# ESP_Batt_Board.net
KiCad netlist of a schematic drawn in Altium Designer
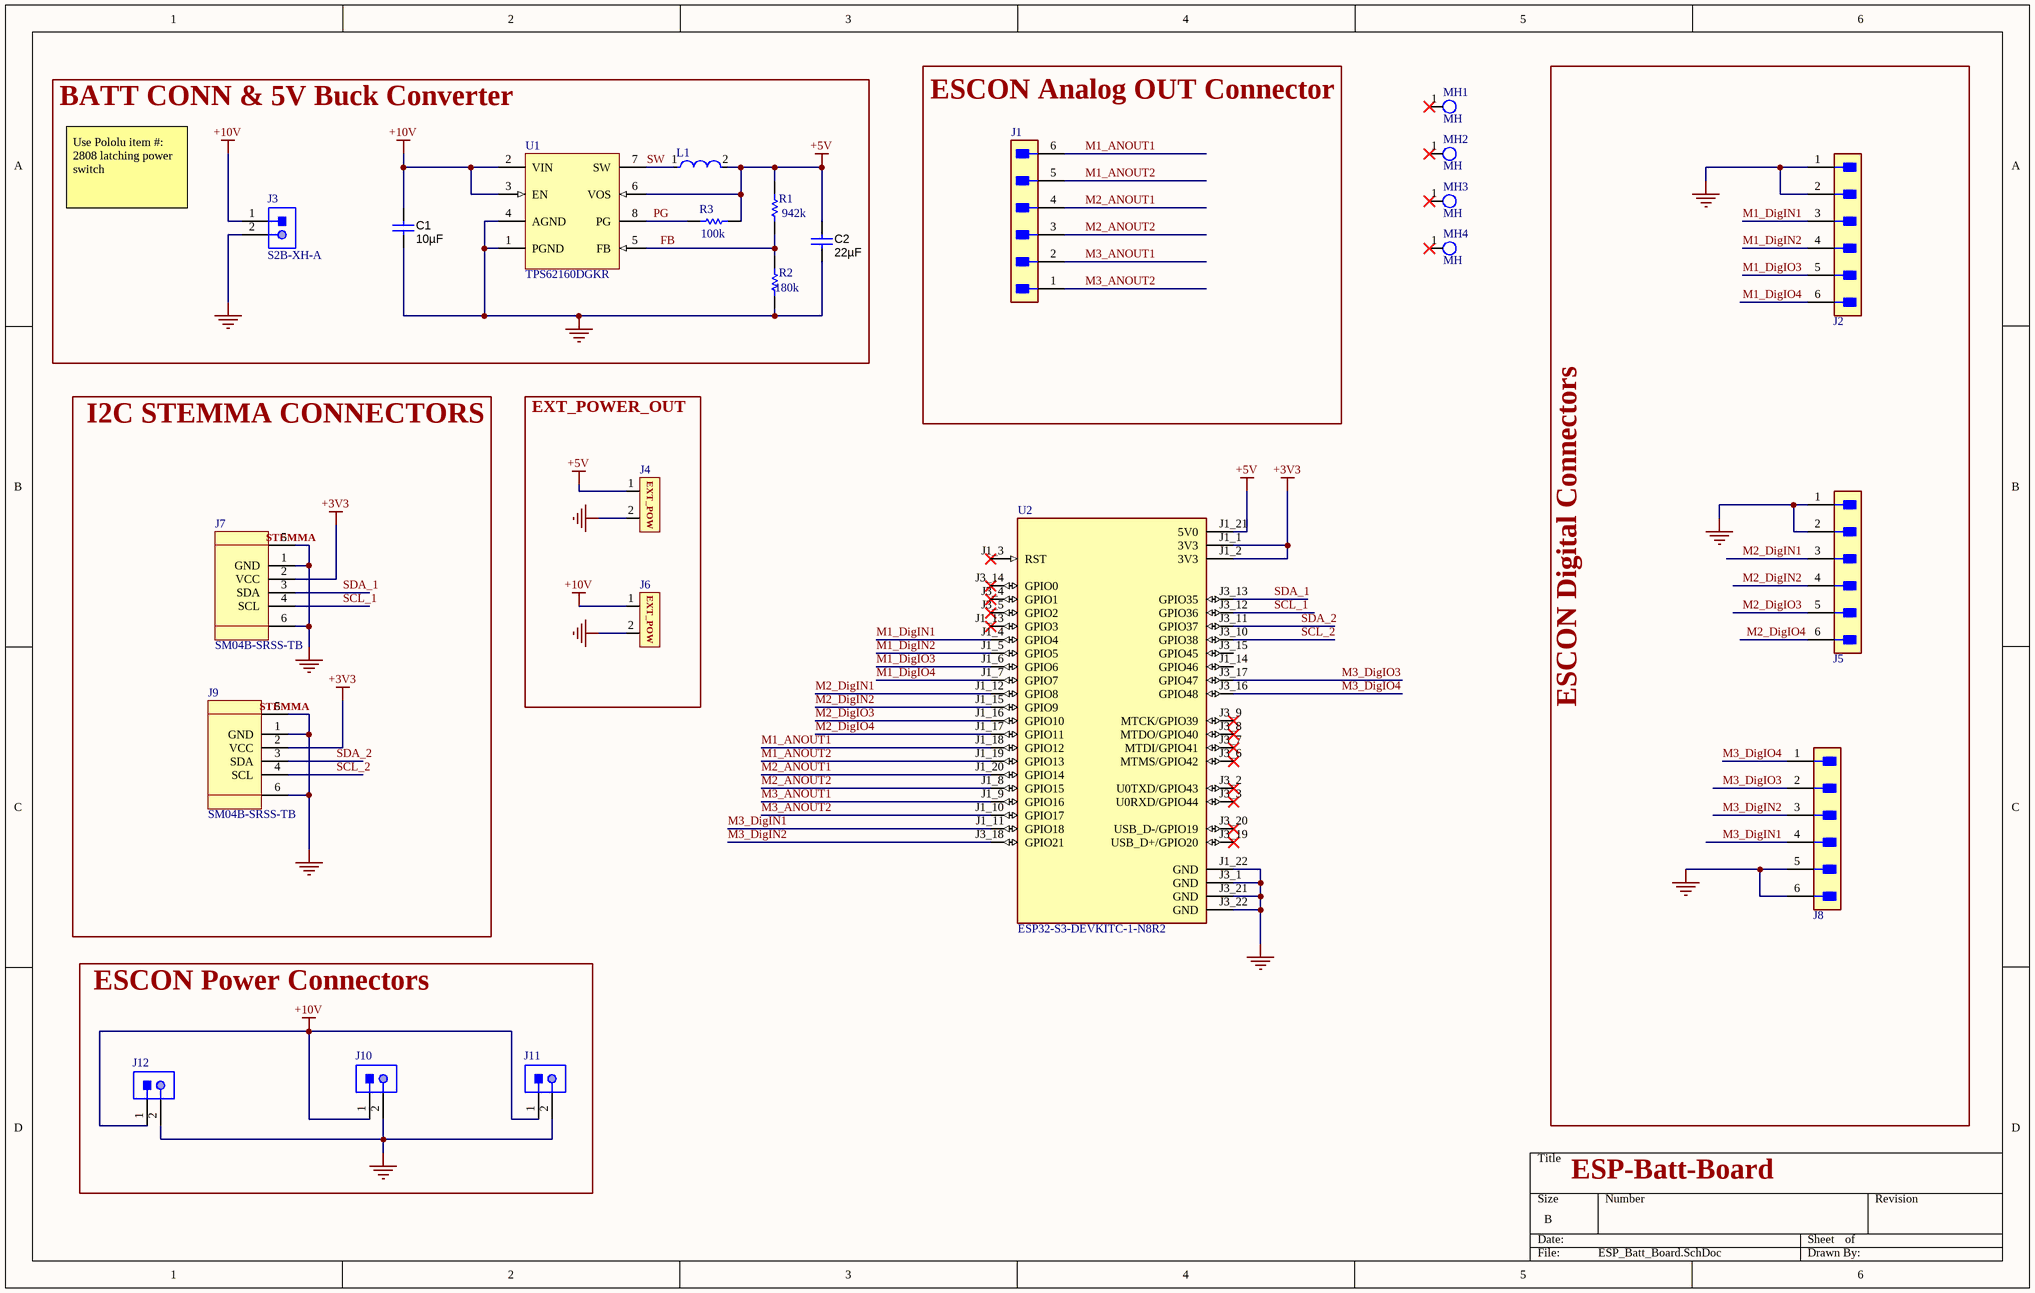
[diagram p0: ESP_Batt_Board.SchDoc]

(export (version "E")
  (design (tool "Eeschema 10.0.6"))
  (components
    (comp (ref "C1")
      (value "C2012X5R1E106K125AB")
      (footprint "CAP_0805")
      (description "CAP, CERM, 10uF, 25V, +/-10%, X5R, 0805")
      (fields
        (field (name "MANUFACTURER") "TDK")
        (field (name "VALUEDISPLAYED") "10µF")
        (field (name "PUBLISHER") "Texas Instruments")
      )
      (libsource (lib "SchematicLib") (part "C2012X5R1E106K125AB"))
    )
    (comp (ref "C2")
      (value "GRM21BR61E226ME44")
      (footprint "CAP_0805")
      (description "CAP, CERM, 22 µF, 25 V, +/- 20%, X5R, 0805")
      (fields (field (name "MANUFACTURER") "MuRata") (field (name "VALUEDISPLAYED") "22µF"))
      (libsource (lib "SchematicLib") (part "GRM21BR61E226ME44"))
    )
    (comp (ref "J1")
      (value "S6B-XH-A (LF)(SN)")
      (footprint "JST-XH-6PIN_RA")
      (description "CONN HEADER THT R/A 6POS 2.5MM")
      (libsource (lib "") (part "S6B-XH-A (LF)(SN)_1"))
    )
    (comp (ref "J2")
      (value "S6B-XH-A (LF)(SN)")
      (footprint "JST-XH-6PIN_RA")
      (description "CONN HEADER THT R/A 6POS 2.5MM")
      (libsource (lib "SchematicLib") (part "S6B-XH-A (LF)(SN)"))
    )
    (comp (ref "J3")
      (value "S2B-XH-A")
      (footprint "JST-S2B-XH-A(LF)(SN)_V")
      (libsource (lib "") (part "S2B-XH-A_1"))
    )
    (comp (ref "J4")
      (value "EXT_POWER_CONN")
      (footprint "PcbLib:POWER")
      (libsource (lib "SchematicLib") (part "EXT_POWER_CONN"))
    )
    (comp (ref "J5")
      (value "S6B-XH-A (LF)(SN)")
      (footprint "JST-XH-6PIN_RA")
      (description "CONN HEADER THT R/A 6POS 2.5MM")
      (libsource (lib "SchematicLib") (part "S6B-XH-A (LF)(SN)"))
    )
    (comp (ref "J6")
      (value "EXT_POWER_CONN")
      (footprint "PcbLib:POWER")
      (libsource (lib "SchematicLib") (part "EXT_POWER_CONN"))
    )
    (comp (ref "J7")
      (value "SM04B-SRSS-TB")
      (footprint "4PIN_STEMMA")
      (libsource (lib "SchematicLib") (part "SM04B-SRSS-TB"))
    )
    (comp (ref "J8")
      (value "S6B-XH-A (LF)(SN)")
      (footprint "JST-XH-6PIN_RA")
      (description "CONN HEADER THT R/A 6POS 2.5MM")
      (libsource (lib "SchematicLib") (part "S6B-XH-A (LF)(SN)"))
    )
    (comp (ref "J9")
      (value "SM04B-SRSS-TB")
      (footprint "4PIN_STEMMA")
      (libsource (lib "SchematicLib") (part "SM04B-SRSS-TB"))
    )
    (comp (ref "J10")
      (value "S2B-XH-A")
      (footprint "JST-S2B-XH-A(LF)(SN)_V")
      (libsource (lib "SchematicLib") (part "S2B-XH-A"))
    )
    (comp (ref "J11")
      (value "S2B-XH-A")
      (footprint "JST-S2B-XH-A(LF)(SN)_V")
      (libsource (lib "SchematicLib") (part "S2B-XH-A"))
    )
    (comp (ref "J12")
      (value "S2B-XH-A")
      (footprint "JST-S2B-XH-A(LF)(SN)_V")
      (libsource (lib "SchematicLib") (part "S2B-XH-A"))
    )
    (comp (ref "L1")
      (value "IHLP1212BZEZ2R2M1Z")
      (footprint "IND_1212")
      (libsource (lib "SchematicLib") (part "IHLP1212BZEZ2R2M1Z"))
    )
    (comp (ref "MH1") (value "MH") (footprint "M2_MTH") (libsource (lib "SchematicLib") (part "M2_MTH")))
    (comp (ref "MH2") (value "MH") (footprint "M2_MTH") (libsource (lib "SchematicLib") (part "M2_MTH")))
    (comp (ref "MH3") (value "MH") (footprint "M2_MTH") (libsource (lib "SchematicLib") (part "M2_MTH")))
    (comp (ref "MH4") (value "MH") (footprint "M2_MTH") (libsource (lib "SchematicLib") (part "M2_MTH")))
    (comp (ref "R1")
      (value "942k")
      (footprint "RES_0603")
      (fields (field (name "R") "942k"))
      (libsource (lib "SchematicLib") (part "RES_0603"))
    )
    (comp (ref "R2")
      (value "180k")
      (footprint "RES_0603")
      (fields (field (name "R") "180k"))
      (libsource (lib "SchematicLib") (part "RES_0603"))
    )
    (comp (ref "R3") (value "100k") (footprint "RES_0603") (libsource (lib "SchematicLib") (part "RES_0603")))
    (comp (ref "U1")
      (value "TPS62160DGKR")
      (footprint "DGK0008A_M")
      (fields (field (name "MANUFACTURER") "Texas Instruments"))
      (libsource (lib "SchematicLib") (part "TPS62160DGKR"))
    )
    (comp (ref "U2")
      (value "ESP32-S3-DEVKITC-1-N8R2")
      (footprint "XCVR_ESP32-S3-DEVKITC-1-N8R2")
      (fields (field (name "MF") "Espressif Systems"))
      (libsource (lib "SchematicLib") (part "ESP32-S3-DEVKITC-1-N8R2"))
    )
  )
  (nets
    (net (code "1") (name "+3V3") (class "Default")
      (node (ref "J7") (pin "2") (pinfunction "VCC_2") (pintype "passive"))
      (node (ref "J9") (pin "2") (pinfunction "VCC_2") (pintype "passive"))
      (node (ref "U2") (pin "J1_1") (pinfunction "3V3_J1_1") (pintype "power_in"))
      (node (ref "U2") (pin "J1_2") (pinfunction "3V3_J1_2") (pintype "power_in"))
    )
    (net (code "2") (name "+5V") (class "Default")
      (node (ref "C2") (pin "1") (pinfunction "1_1") (pintype "passive"))
      (node (ref "J4") (pin "1") (pinfunction "1_1") (pintype "passive"))
      (node (ref "L1") (pin "2") (pinfunction "2_2") (pintype "passive"))
      (node (ref "R1") (pin "2") (pinfunction "2_2") (pintype "passive"))
      (node (ref "R3") (pin "2") (pinfunction "2_2") (pintype "passive"))
      (node (ref "U1") (pin "6") (pinfunction "VOS_6") (pintype "input"))
      (node (ref "U2") (pin "J1_21") (pinfunction "5V0_J1_21") (pintype "power_in"))
    )
    (net (code "3") (name "+10V") (class "Default")
      (node (ref "C1") (pin "1") (pinfunction "1_1") (pintype "passive"))
      (node (ref "J10") (pin "1") (pinfunction "1_1") (pintype "passive"))
      (node (ref "J11") (pin "1") (pinfunction "1_1") (pintype "passive"))
      (node (ref "J12") (pin "1") (pinfunction "1_1") (pintype "passive"))
      (node (ref "J3") (pin "1") (pinfunction "1_1") (pintype "passive"))
      (node (ref "J6") (pin "1") (pinfunction "1_1") (pintype "passive"))
      (node (ref "U1") (pin "2") (pinfunction "VIN_2") (pintype "power_in"))
      (node (ref "U1") (pin "3") (pinfunction "EN_3") (pintype "input"))
    )
    (net (code "4") (name "/FB") (class "Default")
      (node (ref "R1") (pin "1") (pinfunction "1_1") (pintype "passive"))
      (node (ref "R2") (pin "2") (pinfunction "2_2") (pintype "passive"))
      (node (ref "U1") (pin "5") (pinfunction "FB_5") (pintype "input"))
    )
    (net (code "5") (name "/M1_ANOUT1") (class "Default")
      (node (ref "J1") (pin "6") (pinfunction "6_6") (pintype "passive"))
      (node (ref "U2") (pin "J1_18") (pinfunction "GPIO12_J1_18") (pintype "bidirectional"))
    )
    (net (code "6") (name "/M1_ANOUT2") (class "Default")
      (node (ref "J1") (pin "5") (pinfunction "5_5") (pintype "passive"))
      (node (ref "U2") (pin "J1_19") (pinfunction "GPIO13_J1_19") (pintype "bidirectional"))
    )
    (net (code "7") (name "/M1_DigIN1") (class "Default")
      (node (ref "J2") (pin "3") (pinfunction "3_3") (pintype "passive"))
      (node (ref "U2") (pin "J1_4") (pinfunction "GPIO4_J1_4") (pintype "bidirectional"))
    )
    (net (code "8") (name "/M1_DigIN2") (class "Default")
      (node (ref "J2") (pin "4") (pinfunction "4_4") (pintype "passive"))
      (node (ref "U2") (pin "J1_5") (pinfunction "GPIO5_J1_5") (pintype "bidirectional"))
    )
    (net (code "9") (name "/M1_DigIO3") (class "Default")
      (node (ref "J2") (pin "5") (pinfunction "5_5") (pintype "passive"))
      (node (ref "U2") (pin "J1_6") (pinfunction "GPIO6_J1_6") (pintype "bidirectional"))
    )
    (net (code "10") (name "/M1_DigIO4") (class "Default")
      (node (ref "J2") (pin "6") (pinfunction "6_6") (pintype "passive"))
      (node (ref "U2") (pin "J1_7") (pinfunction "GPIO7_J1_7") (pintype "bidirectional"))
    )
    (net (code "11") (name "/M2_ANOUT1") (class "Default")
      (node (ref "J1") (pin "4") (pinfunction "4_4") (pintype "passive"))
      (node (ref "U2") (pin "J1_20") (pinfunction "GPIO14_J1_20") (pintype "bidirectional"))
    )
    (net (code "12") (name "/M2_ANOUT2") (class "Default")
      (node (ref "J1") (pin "3") (pinfunction "3_3") (pintype "passive"))
      (node (ref "U2") (pin "J1_8") (pinfunction "GPIO15_J1_8") (pintype "bidirectional"))
    )
    (net (code "13") (name "/M2_DigIN1") (class "Default")
      (node (ref "J5") (pin "3") (pinfunction "3_3") (pintype "passive"))
      (node (ref "U2") (pin "J1_12") (pinfunction "GPIO8_J1_12") (pintype "bidirectional"))
    )
    (net (code "14") (name "/M2_DigIN2") (class "Default")
      (node (ref "J5") (pin "4") (pinfunction "4_4") (pintype "passive"))
      (node (ref "U2") (pin "J1_15") (pinfunction "GPIO9_J1_15") (pintype "bidirectional"))
    )
    (net (code "15") (name "/M2_DigIO3") (class "Default")
      (node (ref "J5") (pin "5") (pinfunction "5_5") (pintype "passive"))
      (node (ref "U2") (pin "J1_16") (pinfunction "GPIO10_J1_16") (pintype "bidirectional"))
    )
    (net (code "16") (name "/M2_DigIO4") (class "Default")
      (node (ref "J5") (pin "6") (pinfunction "6_6") (pintype "passive"))
      (node (ref "U2") (pin "J1_17") (pinfunction "GPIO11_J1_17") (pintype "bidirectional"))
    )
    (net (code "17") (name "/M3_ANOUT1") (class "Default")
      (node (ref "J1") (pin "2") (pinfunction "2_2") (pintype "passive"))
      (node (ref "U2") (pin "J1_9") (pinfunction "GPIO16_J1_9") (pintype "bidirectional"))
    )
    (net (code "18") (name "/M3_ANOUT2") (class "Default")
      (node (ref "J1") (pin "1") (pinfunction "1_1") (pintype "passive"))
      (node (ref "U2") (pin "J1_10") (pinfunction "GPIO17_J1_10") (pintype "bidirectional"))
    )
    (net (code "19") (name "/M3_DigIN1") (class "Default")
      (node (ref "J8") (pin "4") (pinfunction "4_4") (pintype "passive"))
      (node (ref "U2") (pin "J1_11") (pinfunction "GPIO18_J1_11") (pintype "bidirectional"))
    )
    (net (code "20") (name "/M3_DigIN2") (class "Default")
      (node (ref "J8") (pin "3") (pinfunction "3_3") (pintype "passive"))
      (node (ref "U2") (pin "J3_18") (pinfunction "GPIO21_J3_18") (pintype "bidirectional"))
    )
    (net (code "21") (name "/M3_DigIO3") (class "Default")
      (node (ref "J8") (pin "2") (pinfunction "2_2") (pintype "passive"))
      (node (ref "U2") (pin "J3_17") (pinfunction "GPIO47_J3_17") (pintype "bidirectional"))
    )
    (net (code "22") (name "/M3_DigIO4") (class "Default")
      (node (ref "J8") (pin "1") (pinfunction "1_1") (pintype "passive"))
      (node (ref "U2") (pin "J3_16") (pinfunction "GPIO48_J3_16") (pintype "bidirectional"))
    )
    (net (code "23") (name "/PG") (class "Default")
      (node (ref "R3") (pin "1") (pinfunction "1_1") (pintype "passive"))
      (node (ref "U1") (pin "8") (pinfunction "PG_8") (pintype "tri_state"))
    )
    (net (code "24") (name "/SCL_1") (class "Default")
      (node (ref "J7") (pin "4") (pinfunction "SCL_4") (pintype "passive"))
      (node (ref "U2") (pin "J3_12") (pinfunction "GPIO36_J3_12") (pintype "bidirectional"))
    )
    (net (code "25") (name "/SCL_2") (class "Default")
      (node (ref "J9") (pin "4") (pinfunction "SCL_4") (pintype "passive"))
      (node (ref "U2") (pin "J3_10") (pinfunction "GPIO38_J3_10") (pintype "bidirectional"))
    )
    (net (code "26") (name "/SDA_1") (class "Default")
      (node (ref "J7") (pin "3") (pinfunction "SDA_3") (pintype "passive"))
      (node (ref "U2") (pin "J3_13") (pinfunction "GPIO35_J3_13") (pintype "bidirectional"))
    )
    (net (code "27") (name "/SDA_2") (class "Default")
      (node (ref "J9") (pin "3") (pinfunction "SDA_3") (pintype "passive"))
      (node (ref "U2") (pin "J3_11") (pinfunction "GPIO37_J3_11") (pintype "bidirectional"))
    )
    (net (code "28") (name "/SW") (class "Default")
      (node (ref "L1") (pin "1") (pinfunction "1_1") (pintype "passive"))
      (node (ref "U1") (pin "7") (pinfunction "SW_7") (pintype "power_in"))
    )
    (net (code "29") (name "GND") (class "Default")
      (node (ref "C1") (pin "2") (pinfunction "2_2") (pintype "passive"))
      (node (ref "C2") (pin "2") (pinfunction "2_2") (pintype "passive"))
      (node (ref "J10") (pin "2") (pinfunction "2_2") (pintype "passive"))
      (node (ref "J11") (pin "2") (pinfunction "2_2") (pintype "passive"))
      (node (ref "J12") (pin "2") (pinfunction "2_2") (pintype "passive"))
      (node (ref "J2") (pin "1") (pinfunction "1_1") (pintype "passive"))
      (node (ref "J2") (pin "2") (pinfunction "2_2") (pintype "passive"))
      (node (ref "J3") (pin "2") (pinfunction "2_2") (pintype "passive"))
      (node (ref "J4") (pin "2") (pinfunction "2_2") (pintype "passive"))
      (node (ref "J5") (pin "1") (pinfunction "1_1") (pintype "passive"))
      (node (ref "J5") (pin "2") (pinfunction "2_2") (pintype "passive"))
      (node (ref "J6") (pin "2") (pinfunction "2_2") (pintype "passive"))
      (node (ref "J7") (pin "1") (pinfunction "GND_1") (pintype "passive"))
      (node (ref "J7") (pin "5") (pinfunction "5_5") (pintype "passive"))
      (node (ref "J7") (pin "6") (pinfunction "6_6") (pintype "passive"))
      (node (ref "J8") (pin "5") (pinfunction "5_5") (pintype "passive"))
      (node (ref "J8") (pin "6") (pinfunction "6_6") (pintype "passive"))
      (node (ref "J9") (pin "1") (pinfunction "GND_1") (pintype "passive"))
      (node (ref "J9") (pin "5") (pinfunction "5_5") (pintype "passive"))
      (node (ref "J9") (pin "6") (pinfunction "6_6") (pintype "passive"))
      (node (ref "R2") (pin "1") (pinfunction "1_1") (pintype "passive"))
      (node (ref "U1") (pin "1") (pinfunction "PGND_1") (pintype "power_in"))
      (node (ref "U1") (pin "4") (pinfunction "AGND_4") (pintype "power_in"))
      (node (ref "U2") (pin "J1_22") (pinfunction "GND_J1_22") (pintype "power_in"))
      (node (ref "U2") (pin "J3_1") (pinfunction "GND_J3_1") (pintype "power_in"))
      (node (ref "U2") (pin "J3_21") (pinfunction "GND_J3_21") (pintype "power_in"))
      (node (ref "U2") (pin "J3_22") (pinfunction "GND_J3_22") (pintype "power_in"))
    )
    (net (code "30") (name "unconnected-(MH1-Pad1)") (class "Default")
      (node (ref "MH1") (pin "1") (pinfunction "1_1") (pintype "passive+no_connect"))
    )
    (net (code "31") (name "unconnected-(MH2-Pad1)") (class "Default")
      (node (ref "MH2") (pin "1") (pinfunction "1_1") (pintype "passive+no_connect"))
    )
    (net (code "32") (name "unconnected-(MH3-Pad1)") (class "Default")
      (node (ref "MH3") (pin "1") (pinfunction "1_1") (pintype "passive+no_connect"))
    )
    (net (code "33") (name "unconnected-(MH4-Pad1)") (class "Default")
      (node (ref "MH4") (pin "1") (pinfunction "1_1") (pintype "passive+no_connect"))
    )
    (net (code "34") (name "unconnected-(U2-GPIO0-PadJ3_14)") (class "Default")
      (node (ref "U2") (pin "J3_14") (pinfunction "GPIO0_J3_14") (pintype "bidirectional+no_connect"))
    )
    (net (code "35") (name "unconnected-(U2-GPIO1-PadJ3_4)") (class "Default")
      (node (ref "U2") (pin "J3_4") (pinfunction "GPIO1_J3_4") (pintype "bidirectional+no_connect"))
    )
    (net (code "36") (name "unconnected-(U2-GPIO2-PadJ3_5)") (class "Default")
      (node (ref "U2") (pin "J3_5") (pinfunction "GPIO2_J3_5") (pintype "bidirectional+no_connect"))
    )
    (net (code "37") (name "unconnected-(U2-GPIO3-PadJ1_13)") (class "Default")
      (node (ref "U2") (pin "J1_13") (pinfunction "GPIO3_J1_13") (pintype "bidirectional+no_connect"))
    )
    (net (code "38") (name "unconnected-(U2-GPIO45-PadJ3_15)") (class "Default")
      (node (ref "U2") (pin "J3_15") (pinfunction "GPIO45_J3_15") (pintype "bidirectional"))
    )
    (net (code "39") (name "unconnected-(U2-GPIO46-PadJ1_14)") (class "Default")
      (node (ref "U2") (pin "J1_14") (pinfunction "GPIO46_J1_14") (pintype "bidirectional"))
    )
    (net (code "40") (name "unconnected-(U2-MTCK{slash}GPIO39-PadJ3_9)") (class "Default")
      (node (ref "U2") (pin "J3_9") (pinfunction "MTCK/GPIO39_J3_9") (pintype "bidirectional+no_connect"))
    )
    (net (code "41") (name "unconnected-(U2-MTDI{slash}GPIO41-PadJ3_7)") (class "Default")
      (node (ref "U2") (pin "J3_7") (pinfunction "MTDI/GPIO41_J3_7") (pintype "bidirectional+no_connect"))
    )
    (net (code "42") (name "unconnected-(U2-MTDO{slash}GPIO40-PadJ3_8)") (class "Default")
      (node (ref "U2") (pin "J3_8") (pinfunction "MTDO/GPIO40_J3_8") (pintype "bidirectional+no_connect"))
    )
    (net (code "43") (name "unconnected-(U2-MTMS{slash}GPIO42-PadJ3_6)") (class "Default")
      (node (ref "U2") (pin "J3_6") (pinfunction "MTMS/GPIO42_J3_6") (pintype "bidirectional+no_connect"))
    )
    (net (code "44") (name "unconnected-(U2-RST-PadJ1_3)") (class "Default")
      (node (ref "U2") (pin "J1_3") (pinfunction "RST_J1_3") (pintype "input+no_connect"))
    )
    (net (code "45") (name "unconnected-(U2-U0RXD{slash}GPIO44-PadJ3_3)") (class "Default")
      (node (ref "U2") (pin "J3_3") (pinfunction "U0RXD/GPIO44_J3_3") (pintype "bidirectional+no_connect"))
    )
    (net (code "46") (name "unconnected-(U2-U0TXD{slash}GPIO43-PadJ3_2)") (class "Default")
      (node (ref "U2") (pin "J3_2") (pinfunction "U0TXD/GPIO43_J3_2") (pintype "bidirectional+no_connect"))
    )
    (net (code "47") (name "unconnected-(U2-USB_D+{slash}GPIO20-PadJ3_19)") (class "Default")
      (node (ref "U2") (pin "J3_19") (pinfunction "USB_D+/GPIO20_J3_19") (pintype "bidirectional+no_connect"))
    )
    (net (code "48") (name "unconnected-(U2-USB_D-{slash}GPIO19-PadJ3_20)") (class "Default")
      (node (ref "U2") (pin "J3_20") (pinfunction "USB_D-/GPIO19_J3_20") (pintype "bidirectional+no_connect"))
    )
  )
)
